# Amplifier.net
KiCad netlist of a schematic drawn in Altium Designer
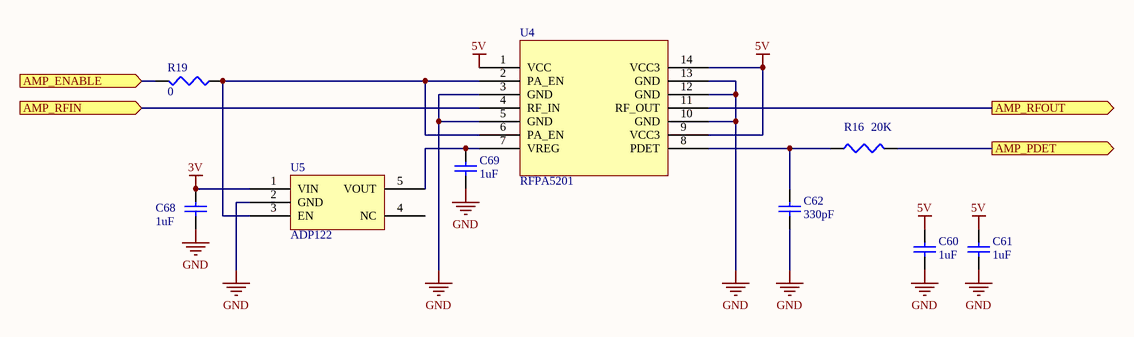
[diagram p0: Amplifier.SchDoc]

(export (version "E")
  (design (tool "Eeschema 10.0.6"))
  (components
    (comp (ref "C60")
      (value "1uF")
      (footprint "1608[0603]")
      (description "Capacitor (Semiconductor SIM Model)")
      (fields (field (name "Comment") "Cap Semi") (field (name "PUBLISHER") "Altium Limited"))
      (libsource (lib "Miscellaneous Devices") (part "Cap Semi"))
    )
    (comp (ref "C61")
      (value "1uF")
      (footprint "1608[0603]")
      (description "Capacitor (Semiconductor SIM Model)")
      (fields (field (name "Comment") "Cap Semi") (field (name "PUBLISHER") "Altium Limited"))
      (libsource (lib "Miscellaneous Devices") (part "Cap Semi"))
    )
    (comp (ref "C62")
      (value "330pF")
      (footprint "1608[0603]")
      (description "Capacitor (Semiconductor SIM Model)")
      (fields (field (name "Comment") "Cap Semi") (field (name "PUBLISHER") "Altium Limited"))
      (libsource (lib "Miscellaneous Devices") (part "Cap Semi"))
    )
    (comp (ref "C68")
      (value "1uF")
      (footprint "1608[0603]")
      (description "Capacitor (Semiconductor SIM Model)")
      (fields (field (name "Comment") "Cap Semi") (field (name "PUBLISHER") "Altium Limited"))
      (libsource (lib "Miscellaneous Devices") (part "Cap Semi"))
    )
    (comp (ref "C69")
      (value "1uF")
      (footprint "1608[0603]")
      (description "Capacitor (Semiconductor SIM Model)")
      (fields (field (name "Comment") "Cap Semi") (field (name "PUBLISHER") "Altium Limited"))
      (libsource (lib "Miscellaneous Devices") (part "Cap Semi"))
    )
    (comp (ref "R16")
      (value "20K")
      (footprint "J1-0603")
      (description "Resistor")
      (fields (field (name "Comment") "Res3") (field (name "PUBLISHER") "Altium Limited"))
      (libsource (lib "Miscellaneous Devices") (part "Res3"))
    )
    (comp (ref "R19")
      (value "0")
      (footprint "J1-0603")
      (description "Resistor")
      (fields (field (name "Comment") "Res3") (field (name "PUBLISHER") "Altium Limited"))
      (libsource (lib "Miscellaneous Devices") (part "Res3"))
    )
    (comp (ref "U4")
      (value "RFPA5201")
      (footprint "MCM14")
      (description "WiFi Power Amplifier Module")
      (libsource (lib "Logic_RF_Component_Symbols") (part "RFPA5201"))
    )
    (comp (ref "U5")
      (value "ADP122")
      (footprint "SOT23-5AM")
      (description "2.9V LDO")
      (libsource (lib "Logic_RF_Component_Symbols") (part "ADP122"))
    )
  )
  (nets
    (net (code "1") (name "/AMP_ENABLE") (class "Default")
      (node (ref "R19") (pin "2") (pinfunction "2_2") (pintype "passive"))
    )
    (net (code "2") (name "/AMP_PDET") (class "Default")
      (node (ref "R16") (pin "2") (pinfunction "2_2") (pintype "passive"))
    )
    (net (code "3") (name "/AMP_RFIN") (class "Default")
      (node (ref "U4") (pin "4") (pinfunction "RF_IN_4") (pintype "passive"))
    )
    (net (code "4") (name "/AMP_RFOUT") (class "Default")
      (node (ref "U4") (pin "11") (pinfunction "RF_OUT_11") (pintype "passive"))
    )
    (net (code "5") (name "3V") (class "Default")
      (node (ref "C68") (pin "2") (pinfunction "2_2") (pintype "passive"))
      (node (ref "U5") (pin "1") (pinfunction "VIN_1") (pintype "passive"))
    )
    (net (code "6") (name "5V") (class "Default")
      (node (ref "C60") (pin "2") (pinfunction "2_2") (pintype "passive"))
      (node (ref "C61") (pin "2") (pinfunction "2_2") (pintype "passive"))
      (node (ref "U4") (pin "1") (pinfunction "VCC_1") (pintype "passive"))
      (node (ref "U4") (pin "14") (pinfunction "VCC3_14") (pintype "passive"))
      (node (ref "U4") (pin "9") (pinfunction "VCC3_9") (pintype "passive"))
    )
    (net (code "7") (name "GND") (class "Default")
      (node (ref "C60") (pin "1") (pinfunction "1_1") (pintype "passive"))
      (node (ref "C61") (pin "1") (pinfunction "1_1") (pintype "passive"))
      (node (ref "C62") (pin "1") (pinfunction "1_1") (pintype "passive"))
      (node (ref "C68") (pin "1") (pinfunction "1_1") (pintype "passive"))
      (node (ref "C69") (pin "1") (pinfunction "1_1") (pintype "passive"))
      (node (ref "U4") (pin "10") (pinfunction "GND_10") (pintype "passive"))
      (node (ref "U4") (pin "12") (pinfunction "GND_12") (pintype "passive"))
      (node (ref "U4") (pin "13") (pinfunction "GND_13") (pintype "passive"))
      (node (ref "U4") (pin "3") (pinfunction "GND_3") (pintype "passive"))
      (node (ref "U4") (pin "5") (pinfunction "GND_5") (pintype "passive"))
      (node (ref "U5") (pin "2") (pinfunction "GND_2") (pintype "passive"))
    )
    (net (code "8") (name "Net-(U4-PDET)") (class "Default")
      (node (ref "C62") (pin "2") (pinfunction "2_2") (pintype "passive"))
      (node (ref "R16") (pin "1") (pinfunction "1_1") (pintype "passive"))
      (node (ref "U4") (pin "8") (pinfunction "PDET_8") (pintype "passive"))
    )
    (net (code "9") (name "Net-(U4-VREG)") (class "Default")
      (node (ref "C69") (pin "2") (pinfunction "2_2") (pintype "passive"))
      (node (ref "U4") (pin "7") (pinfunction "VREG_7") (pintype "passive"))
      (node (ref "U5") (pin "5") (pinfunction "VOUT_5") (pintype "passive"))
    )
    (net (code "10") (name "Net-(U5-EN)") (class "Default")
      (node (ref "R19") (pin "1") (pinfunction "1_1") (pintype "passive"))
      (node (ref "U4") (pin "2") (pinfunction "PA_EN_2") (pintype "passive"))
      (node (ref "U4") (pin "6") (pinfunction "PA_EN_6") (pintype "passive"))
      (node (ref "U5") (pin "3") (pinfunction "EN_3") (pintype "passive"))
    )
    (net (code "11") (name "unconnected-(U5-NC-Pad4)") (class "Default")
      (node (ref "U5") (pin "4") (pinfunction "NC_4") (pintype "passive"))
    )
  )
)
